# HP-noninv.net
KiCad netlist of a schematic drawn in EAGLE
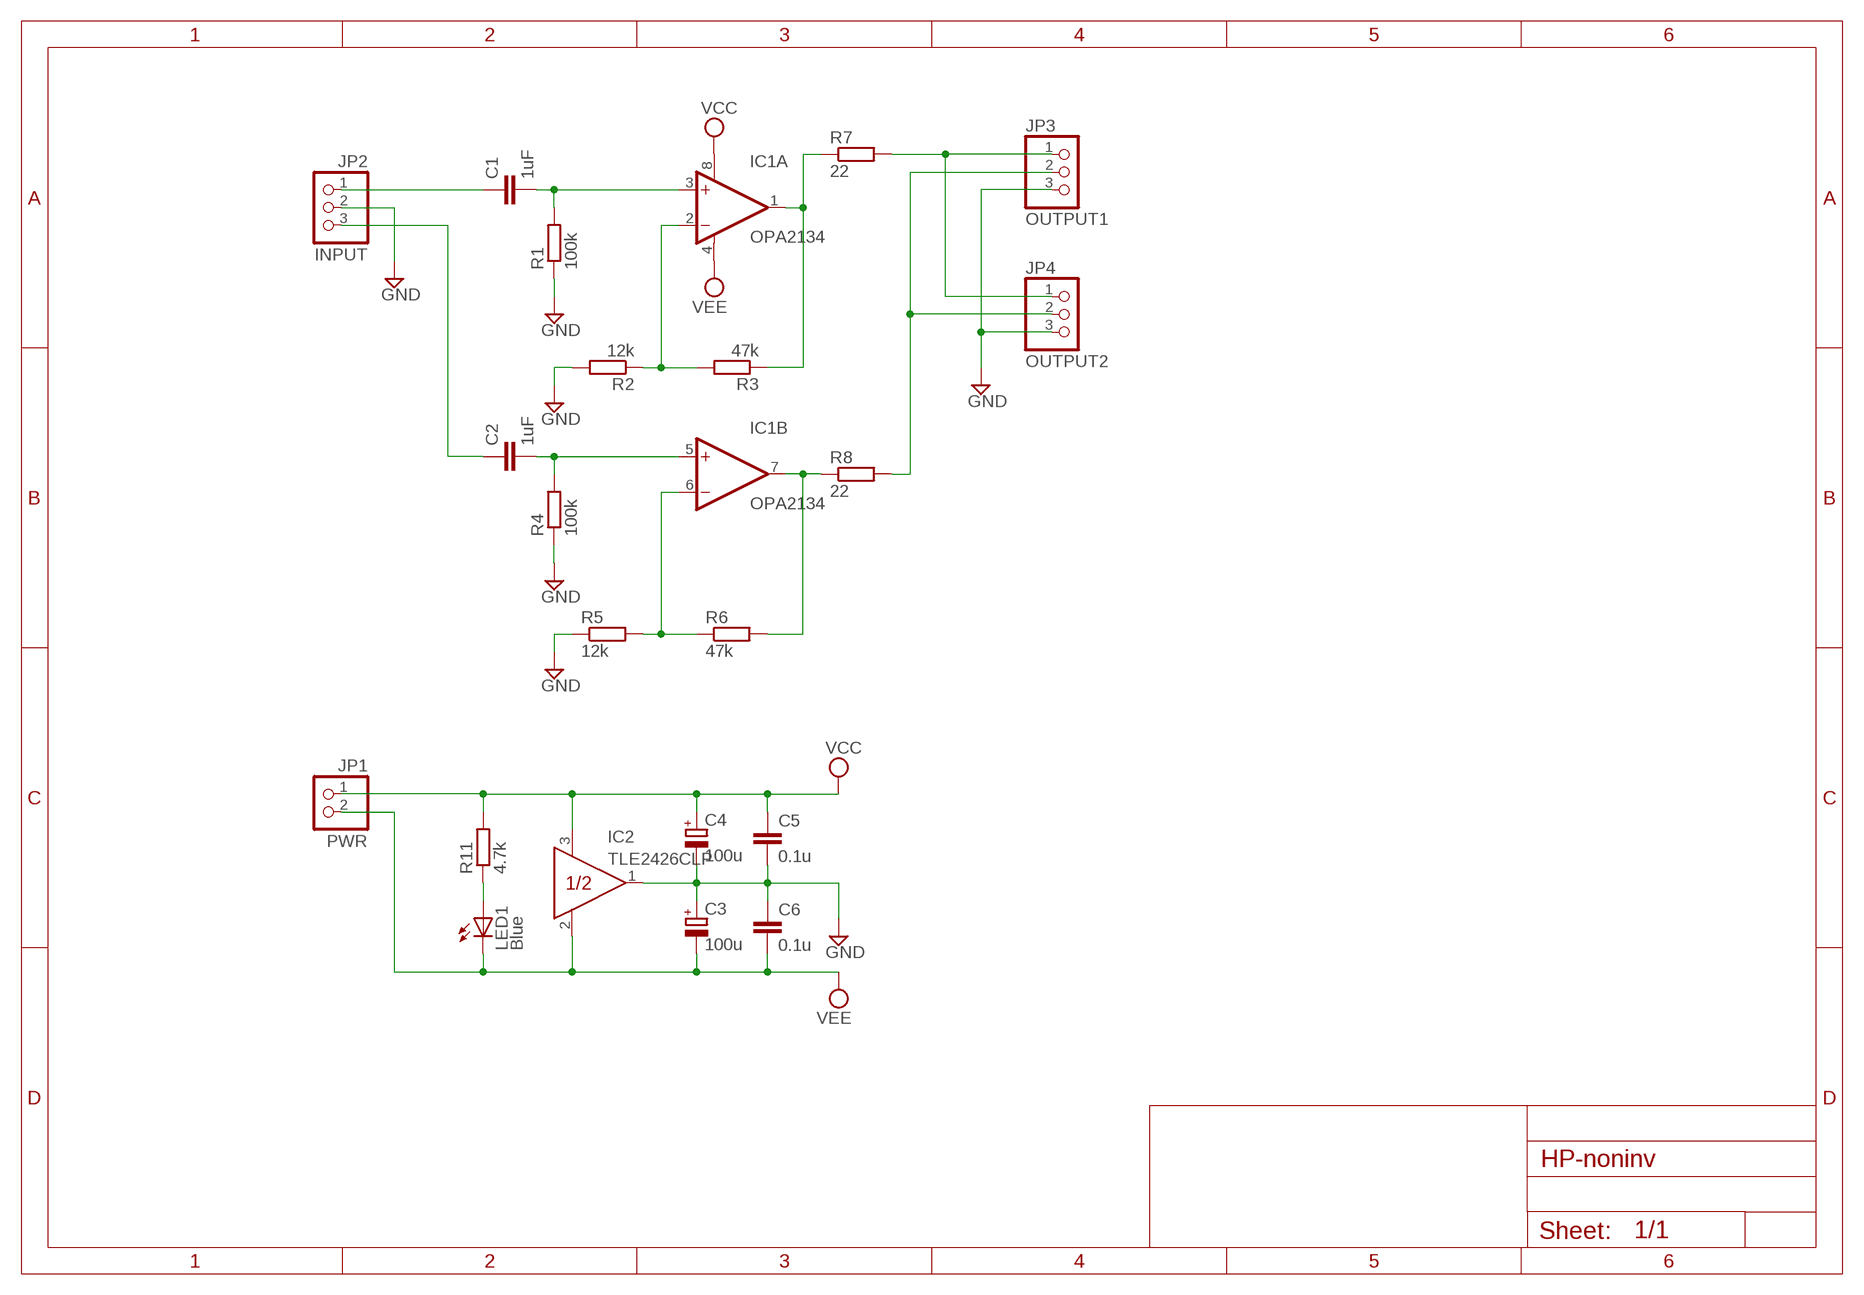
[diagram p0: schematic, sheet 1]

(export (version "E")
  (design (tool "Eeschema 10.0.6"))
  (components
    (comp (ref "C1")
      (value "1uF")
      (footprint "eagle-import:C050-050X075")
      (libsource (lib "eagle-import") (part "C-EU050-050X075"))
    )
    (comp (ref "C2")
      (value "1uF")
      (footprint "eagle-import:C050-050X075")
      (libsource (lib "eagle-import") (part "C-EU050-050X075"))
    )
    (comp (ref "C3")
      (value "100u")
      (footprint "eagle-import:TT5D6L")
      (libsource (lib "eagle-import") (part "CPOL-EUTT5D6L"))
    )
    (comp (ref "C4")
      (value "100u")
      (footprint "eagle-import:TT5D6L")
      (libsource (lib "eagle-import") (part "CPOL-EUTT5D6L"))
    )
    (comp (ref "C5")
      (value "0.1u")
      (footprint "eagle-import:C025-024X044")
      (libsource (lib "eagle-import") (part "C-EU025-024X044"))
    )
    (comp (ref "C6")
      (value "0.1u")
      (footprint "eagle-import:C050-024X044")
      (libsource (lib "eagle-import") (part "C-EU050-024X044"))
    )
    (comp (ref "IC1")
      (value "OPA2134")
      (footprint "eagle-import:DIL08")
      (fields (field (name "MF") "TEXAS INSTRUMENTS") (field (name "MPN") "OPA2134PA"))
      (libsource (lib "eagle-import") (part "OPA2134P"))
    )
    (comp (ref "IC2")
      (value "TLE2426CLP")
      (footprint "eagle-import:TO226AA")
      (libsource (lib "eagle-import") (part "TLE2426LPC"))
    )
    (comp (ref "JP1")
      (value "PWR")
      (footprint "eagle-import:1X02")
      (libsource (lib "eagle-import") (part "PINHD-1X2"))
    )
    (comp (ref "JP2")
      (value "INPUT")
      (footprint "eagle-import:1X03")
      (libsource (lib "eagle-import") (part "PINHD-1X3"))
    )
    (comp (ref "JP3")
      (value "OUTPUT1")
      (footprint "eagle-import:1X03")
      (libsource (lib "eagle-import") (part "PINHD-1X3"))
    )
    (comp (ref "JP4")
      (value "OUTPUT2")
      (footprint "eagle-import:1X03")
      (libsource (lib "eagle-import") (part "PINHD-1X3"))
    )
    (comp (ref "LED1")
      (value "Blue")
      (footprint "eagle-import:LED3MM")
      (libsource (lib "eagle-import") (part "LED3MM"))
    )
    (comp (ref "R1")
      (value "100k")
      (footprint "eagle-import:0207_7")
      (libsource (lib "eagle-import") (part "R-EU_0207/7"))
    )
    (comp (ref "R2")
      (value "12k")
      (footprint "eagle-import:0207_7")
      (libsource (lib "eagle-import") (part "R-EU_0207/7"))
    )
    (comp (ref "R3")
      (value "47k")
      (footprint "eagle-import:0207_7")
      (libsource (lib "eagle-import") (part "R-EU_0207/7"))
    )
    (comp (ref "R4")
      (value "100k")
      (footprint "eagle-import:0207_7")
      (libsource (lib "eagle-import") (part "R-EU_0207/7"))
    )
    (comp (ref "R5")
      (value "12k")
      (footprint "eagle-import:0207_7")
      (libsource (lib "eagle-import") (part "R-EU_0207/7"))
    )
    (comp (ref "R6")
      (value "47k")
      (footprint "eagle-import:0207_7")
      (libsource (lib "eagle-import") (part "R-EU_0207/7"))
    )
    (comp (ref "R7")
      (value "22")
      (footprint "eagle-import:0207_7")
      (libsource (lib "eagle-import") (part "R-EU_0207/7"))
    )
    (comp (ref "R8")
      (value "22")
      (footprint "eagle-import:0207_7")
      (libsource (lib "eagle-import") (part "R-EU_0207/7"))
    )
    (comp (ref "R11")
      (value "4.7k")
      (footprint "eagle-import:0207_7")
      (libsource (lib "eagle-import") (part "R-EU_0207/7"))
    )
  )
  (nets
    (net (code "1") (name "GND") (class "Default")
      (node (ref "C3") (pin "+") (pinfunction "+_+") (pintype "passive"))
      (node (ref "C4") (pin "-") (pinfunction "-_-") (pintype "passive"))
      (node (ref "C5") (pin "2") (pinfunction "2_2") (pintype "passive"))
      (node (ref "C6") (pin "1") (pinfunction "1_1") (pintype "passive"))
      (node (ref "IC2") (pin "1") (pinfunction "OUT_1") (pintype "passive"))
      (node (ref "JP2") (pin "2") (pinfunction "2_2") (pintype "passive"))
      (node (ref "JP3") (pin "3") (pinfunction "3_3") (pintype "passive"))
      (node (ref "JP4") (pin "3") (pinfunction "3_3") (pintype "passive"))
      (node (ref "R1") (pin "1") (pinfunction "1_1") (pintype "passive"))
      (node (ref "R2") (pin "2") (pinfunction "2_2") (pintype "passive"))
      (node (ref "R4") (pin "1") (pinfunction "1_1") (pintype "passive"))
      (node (ref "R5") (pin "1") (pinfunction "1_1") (pintype "passive"))
    )
    (net (code "2") (name "Net-(C1-Pad1)") (class "Default")
      (node (ref "C1") (pin "1") (pinfunction "1_1") (pintype "passive"))
      (node (ref "JP2") (pin "1") (pinfunction "1_1") (pintype "passive"))
    )
    (net (code "3") (name "Net-(C2-Pad1)") (class "Default")
      (node (ref "C2") (pin "1") (pinfunction "1_1") (pintype "passive"))
      (node (ref "JP2") (pin "3") (pinfunction "3_3") (pintype "passive"))
    )
    (net (code "4") (name "Net-(IC1A-+IN)") (class "Default")
      (node (ref "C1") (pin "2") (pinfunction "2_2") (pintype "passive"))
      (node (ref "IC1") (pin "3") (pinfunction "+IN_3") (pintype "input"))
      (node (ref "R1") (pin "2") (pinfunction "2_2") (pintype "passive"))
    )
    (net (code "5") (name "Net-(IC1A--IN)") (class "Default")
      (node (ref "IC1") (pin "2") (pinfunction "-IN_2") (pintype "input"))
      (node (ref "R2") (pin "1") (pinfunction "1_1") (pintype "passive"))
      (node (ref "R3") (pin "2") (pinfunction "2_2") (pintype "passive"))
    )
    (net (code "6") (name "Net-(IC1A-OUT)") (class "Default")
      (node (ref "IC1") (pin "1") (pinfunction "OUT_1") (pintype "output"))
      (node (ref "R3") (pin "1") (pinfunction "1_1") (pintype "passive"))
      (node (ref "R7") (pin "1") (pinfunction "1_1") (pintype "passive"))
    )
    (net (code "7") (name "Net-(IC1B-+IN)") (class "Default")
      (node (ref "C2") (pin "2") (pinfunction "2_2") (pintype "passive"))
      (node (ref "IC1") (pin "5") (pinfunction "+IN_5") (pintype "input"))
      (node (ref "R4") (pin "2") (pinfunction "2_2") (pintype "passive"))
    )
    (net (code "8") (name "Net-(IC1B--IN)") (class "Default")
      (node (ref "IC1") (pin "6") (pinfunction "-IN_6") (pintype "input"))
      (node (ref "R5") (pin "2") (pinfunction "2_2") (pintype "passive"))
      (node (ref "R6") (pin "1") (pinfunction "1_1") (pintype "passive"))
    )
    (net (code "9") (name "Net-(IC1B-OUT)") (class "Default")
      (node (ref "IC1") (pin "7") (pinfunction "OUT_7") (pintype "output"))
      (node (ref "R6") (pin "2") (pinfunction "2_2") (pintype "passive"))
      (node (ref "R8") (pin "1") (pinfunction "1_1") (pintype "passive"))
    )
    (net (code "10") (name "Net-(JP3-Pad1)") (class "Default")
      (node (ref "JP3") (pin "1") (pinfunction "1_1") (pintype "passive"))
      (node (ref "JP4") (pin "1") (pinfunction "1_1") (pintype "passive"))
      (node (ref "R7") (pin "2") (pinfunction "2_2") (pintype "passive"))
    )
    (net (code "11") (name "Net-(JP3-Pad2)") (class "Default")
      (node (ref "JP3") (pin "2") (pinfunction "2_2") (pintype "passive"))
      (node (ref "JP4") (pin "2") (pinfunction "2_2") (pintype "passive"))
      (node (ref "R8") (pin "2") (pinfunction "2_2") (pintype "passive"))
    )
    (net (code "12") (name "Net-(LED1-PadA)") (class "Default")
      (node (ref "LED1") (pin "A") (pinfunction "A_A") (pintype "passive"))
      (node (ref "R11") (pin "1") (pinfunction "1_1") (pintype "passive"))
    )
    (net (code "13") (name "VCC") (class "Default")
      (node (ref "C4") (pin "+") (pinfunction "+_+") (pintype "passive"))
      (node (ref "C5") (pin "1") (pinfunction "1_1") (pintype "passive"))
      (node (ref "IC1") (pin "8") (pinfunction "V+_8") (pintype "power_in"))
      (node (ref "IC2") (pin "3") (pinfunction "IN_3") (pintype "passive"))
      (node (ref "JP1") (pin "1") (pinfunction "1_1") (pintype "passive"))
      (node (ref "R11") (pin "2") (pinfunction "2_2") (pintype "passive"))
    )
    (net (code "14") (name "VEE") (class "Default")
      (node (ref "C3") (pin "-") (pinfunction "-_-") (pintype "passive"))
      (node (ref "C6") (pin "2") (pinfunction "2_2") (pintype "passive"))
      (node (ref "IC1") (pin "4") (pinfunction "V-_4") (pintype "power_in"))
      (node (ref "IC2") (pin "2") (pinfunction "COM_2") (pintype "passive"))
      (node (ref "JP1") (pin "2") (pinfunction "2_2") (pintype "passive"))
      (node (ref "LED1") (pin "K") (pinfunction "C_K") (pintype "passive"))
    )
  )
)
